# wireless_test.net
KiCad netlist of a schematic drawn in EAGLE
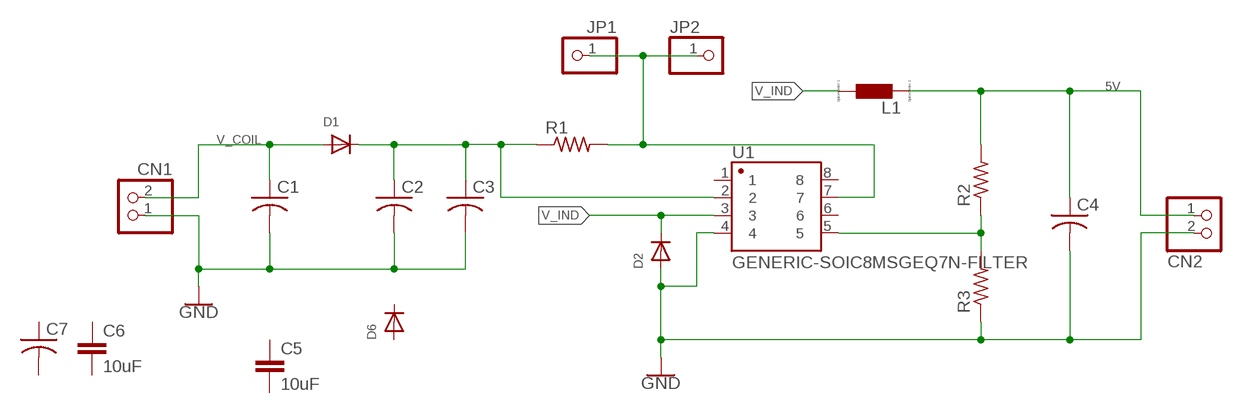
[diagram p0: schematic, sheet 1]

(export (version "E")
  (design (tool "Eeschema 10.0.6"))
  (components
    (comp (ref "C1")
      (value "C-USC0805")
      (footprint "eagle-import:C0805")
      (libsource (lib "eagle-import") (part "C-USC0805"))
    )
    (comp (ref "C2")
      (value "C-USC0805")
      (footprint "eagle-import:C0805")
      (libsource (lib "eagle-import") (part "C-USC0805"))
    )
    (comp (ref "C3")
      (value "C-USC0805")
      (footprint "eagle-import:C0805")
      (libsource (lib "eagle-import") (part "C-USC0805"))
    )
    (comp (ref "C4")
      (value "C-USC0805")
      (footprint "eagle-import:C0805")
      (libsource (lib "eagle-import") (part "C-USC0805"))
    )
    (comp (ref "C5")
      (value "10uF")
      (footprint "eagle-import:0805")
      (libsource (lib "eagle-import") (part "10UF-0805-10V-10%"))
    )
    (comp (ref "C6")
      (value "10uF")
      (footprint "eagle-import:1206")
      (libsource (lib "eagle-import") (part "10UF-1206-6.3V-20%"))
    )
    (comp (ref "C7")
      (value "C-USC1206")
      (footprint "eagle-import:C1206")
      (libsource (lib "eagle-import") (part "C-USC1206"))
    )
    (comp (ref "CN1")
      (value "JST_2PIN-THM-RA")
      (footprint "eagle-import:JST-PH-2-THM-RA")
      (libsource (lib "eagle-import") (part "JST_2PIN-THM-RA"))
    )
    (comp (ref "CN2")
      (value "JST_2PIN-THM-RA")
      (footprint "eagle-import:JST-PH-2-THM-RA")
      (libsource (lib "eagle-import") (part "JST_2PIN-THM-RA"))
    )
    (comp (ref "D1")
      (value "DIODESMA")
      (footprint "eagle-import:SMADIODE")
      (libsource (lib "eagle-import") (part "DIODESMA"))
    )
    (comp (ref "D2")
      (value "DIODESOD-523")
      (footprint "eagle-import:SOD-523")
      (libsource (lib "eagle-import") (part "DIODESOD-523"))
    )
    (comp (ref "D6")
      (value "DIODE_SOD-123FL")
      (footprint "eagle-import:SOD-123FL")
      (libsource (lib "eagle-import") (part "DIODE_SOD-123FL"))
    )
    (comp (ref "JP1")
      (value "PINHD-1X1")
      (footprint "eagle-import:1X01")
      (libsource (lib "eagle-import") (part "PINHD-1X1"))
    )
    (comp (ref "JP2")
      (value "PINHD-1X1")
      (footprint "eagle-import:1X01")
      (libsource (lib "eagle-import") (part "PINHD-1X1"))
    )
    (comp (ref "L1")
      (value "LL3230M")
      (footprint "eagle-import:L3230M")
      (libsource (lib "eagle-import") (part "LL3230M"))
    )
    (comp (ref "R1")
      (value "R-US_R0603")
      (footprint "eagle-import:R0603")
      (libsource (lib "eagle-import") (part "R-US_R0603"))
    )
    (comp (ref "R2")
      (value "R-US_R0603")
      (footprint "eagle-import:R0603")
      (libsource (lib "eagle-import") (part "R-US_R0603"))
    )
    (comp (ref "R3")
      (value "R-US_R0603")
      (footprint "eagle-import:R0603")
      (libsource (lib "eagle-import") (part "R-US_R0603"))
    )
    (comp (ref "U1")
      (value "GENERIC-SOIC8MSGEQ7N-FILTER")
      (footprint "eagle-import:SO08")
      (libsource (lib "eagle-import") (part "GENERIC-SOIC8MSGEQ7N-FILTER"))
    )
  )
  (nets
    (net (code "1") (name "/5V") (class "Default")
      (node (ref "C4") (pin "1") (pinfunction "1_1") (pintype "passive"))
      (node (ref "CN2") (pin "1") (pinfunction "2_1") (pintype "passive"))
      (node (ref "L1") (pin "2") (pinfunction "2_2") (pintype "passive"))
      (node (ref "R2") (pin "2") (pinfunction "2_2") (pintype "passive"))
    )
    (net (code "2") (name "/V_COIL") (class "Default")
      (node (ref "C1") (pin "1") (pinfunction "1_1") (pintype "passive"))
      (node (ref "CN1") (pin "2") (pinfunction "1_2") (pintype "passive"))
      (node (ref "D1") (pin "A") (pinfunction "A_A") (pintype "passive"))
    )
    (net (code "3") (name "GND") (class "Default")
      (node (ref "C1") (pin "2") (pinfunction "2_2") (pintype "passive"))
      (node (ref "C2") (pin "2") (pinfunction "2_2") (pintype "passive"))
      (node (ref "C3") (pin "2") (pinfunction "2_2") (pintype "passive"))
      (node (ref "C4") (pin "2") (pinfunction "2_2") (pintype "passive"))
      (node (ref "CN1") (pin "1") (pinfunction "2_1") (pintype "passive"))
      (node (ref "CN2") (pin "2") (pinfunction "1_2") (pintype "passive"))
      (node (ref "D2") (pin "A") (pinfunction "A_A") (pintype "passive"))
      (node (ref "R3") (pin "1") (pinfunction "1_1") (pintype "passive"))
      (node (ref "U1") (pin "4") (pinfunction "4_4") (pintype "bidirectional"))
    )
    (net (code "4") (name "Net-(C2-Pad1)") (class "Default")
      (node (ref "C2") (pin "1") (pinfunction "1_1") (pintype "passive"))
      (node (ref "C3") (pin "1") (pinfunction "1_1") (pintype "passive"))
      (node (ref "D1") (pin "C") (pinfunction "C_C") (pintype "passive"))
      (node (ref "R1") (pin "1") (pinfunction "1_1") (pintype "passive"))
      (node (ref "U1") (pin "2") (pinfunction "2_2") (pintype "bidirectional"))
    )
    (net (code "5") (name "Net-(JP1-Pad1)") (class "Default")
      (node (ref "JP1") (pin "1") (pinfunction "1_1") (pintype "passive"))
      (node (ref "JP2") (pin "1") (pinfunction "1_1") (pintype "passive"))
      (node (ref "R1") (pin "2") (pinfunction "2_2") (pintype "passive"))
      (node (ref "U1") (pin "7") (pinfunction "7_7") (pintype "bidirectional"))
    )
    (net (code "6") (name "Net-(R2-Pad1)") (class "Default")
      (node (ref "R2") (pin "1") (pinfunction "1_1") (pintype "passive"))
      (node (ref "R3") (pin "2") (pinfunction "2_2") (pintype "passive"))
      (node (ref "U1") (pin "5") (pinfunction "5_5") (pintype "bidirectional"))
    )
    (net (code "7") (name "V_IND") (class "Default")
      (node (ref "D2") (pin "K") (pinfunction "C_K") (pintype "passive"))
      (node (ref "L1") (pin "1") (pinfunction "1_1") (pintype "passive"))
      (node (ref "U1") (pin "3") (pinfunction "3_3") (pintype "bidirectional"))
    )
    (net (code "8") (name "unconnected-(C5-Pad1)") (class "Default")
      (node (ref "C5") (pin "1") (pinfunction "1_1") (pintype "passive"))
    )
    (net (code "9") (name "unconnected-(C5-Pad2)") (class "Default")
      (node (ref "C5") (pin "2") (pinfunction "2_2") (pintype "passive"))
    )
    (net (code "10") (name "unconnected-(C6-Pad1)") (class "Default")
      (node (ref "C6") (pin "1") (pinfunction "1_1") (pintype "passive"))
    )
    (net (code "11") (name "unconnected-(C6-Pad2)") (class "Default")
      (node (ref "C6") (pin "2") (pinfunction "2_2") (pintype "passive"))
    )
    (net (code "12") (name "unconnected-(C7-Pad1)") (class "Default")
      (node (ref "C7") (pin "1") (pinfunction "1_1") (pintype "passive"))
    )
    (net (code "13") (name "unconnected-(C7-Pad2)") (class "Default")
      (node (ref "C7") (pin "2") (pinfunction "2_2") (pintype "passive"))
    )
    (net (code "14") (name "unconnected-(D6-PadA)") (class "Default")
      (node (ref "D6") (pin "A") (pinfunction "A_A") (pintype "passive"))
    )
    (net (code "15") (name "unconnected-(D6-PadC)") (class "Default")
      (node (ref "D6") (pin "C") (pinfunction "C_C") (pintype "passive"))
    )
    (net (code "16") (name "unconnected-(U1-Pad1)") (class "Default")
      (node (ref "U1") (pin "1") (pinfunction "1_1") (pintype "bidirectional"))
    )
    (net (code "17") (name "unconnected-(U1-Pad6)") (class "Default")
      (node (ref "U1") (pin "6") (pinfunction "6_6") (pintype "bidirectional"))
    )
    (net (code "18") (name "unconnected-(U1-Pad8)") (class "Default")
      (node (ref "U1") (pin "8") (pinfunction "8_8") (pintype "bidirectional"))
    )
  )
)
